# INA219_CH4.net
KiCad netlist of a schematic drawn in Altium Designer
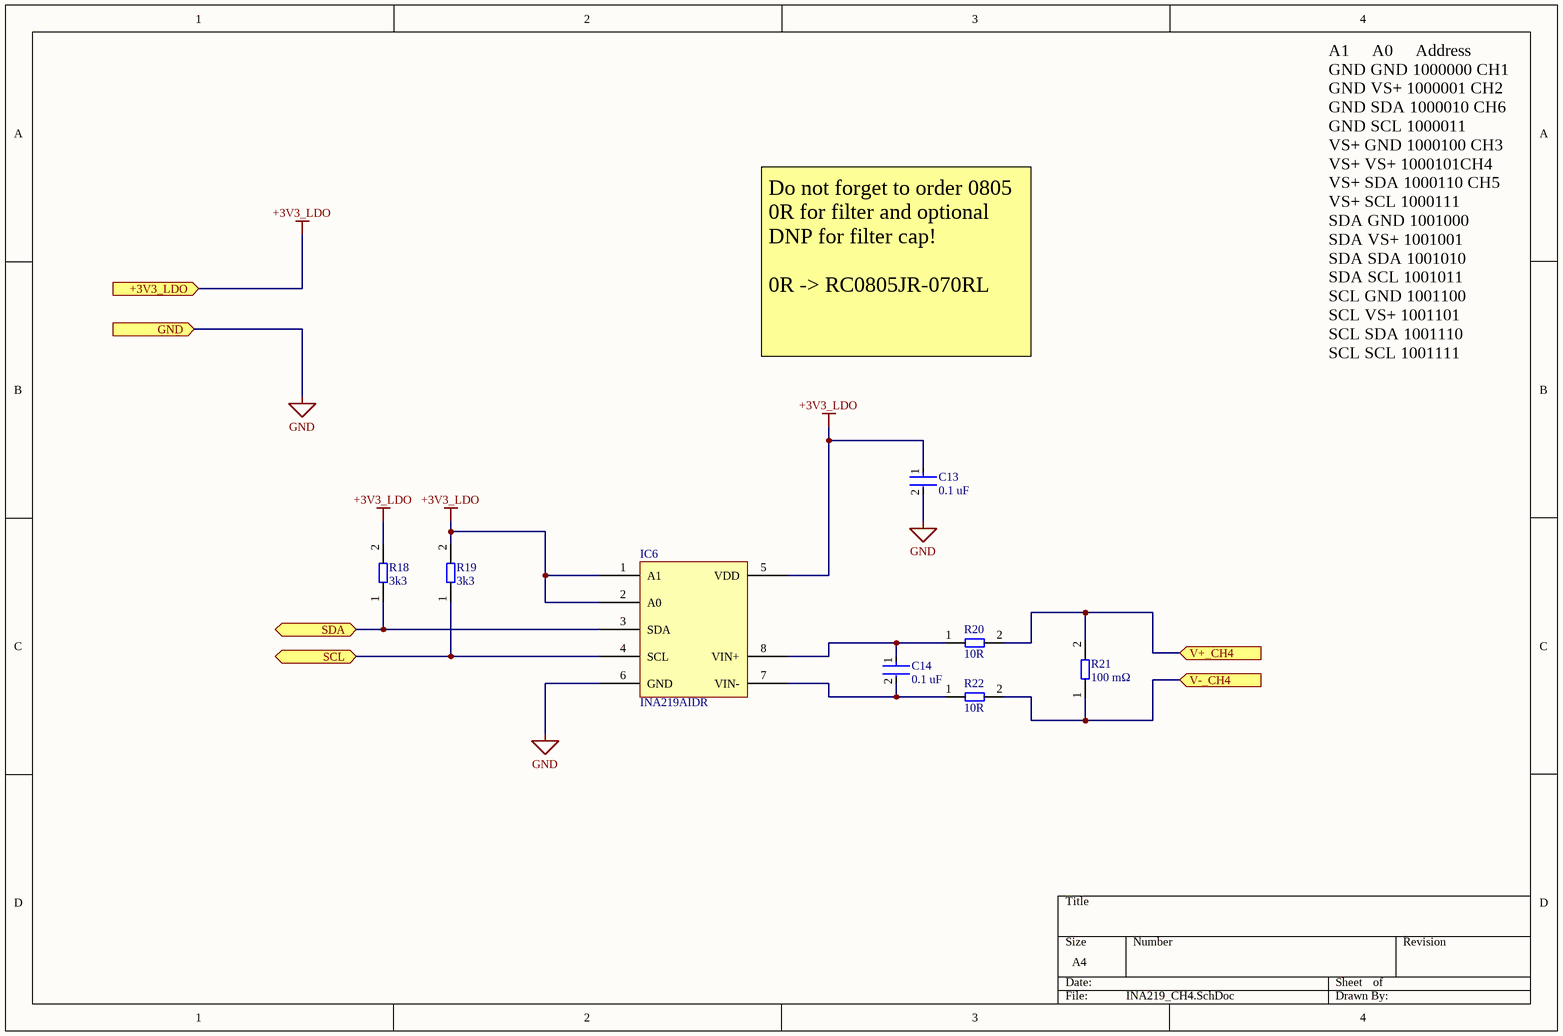
[diagram p0: INA219_CH4.SchDoc]

(export (version "E")
  (design (tool "Eeschema 10.0.6"))
  (components
    (comp (ref "C13")
      (value "0.1 uF")
      (footprint "FP-C0805C-DN-MFG")
      (description "C0805 0.10 μF X7R 30ppm/°C 20.00% 50 V C0805C104M5RAC")
      (fields
        (field (name "MANUFACTURER PART NUMBER") "C0805C104M5RAC")
        (field (name "MANUFACTURER") "KEMET")
      )
      (libsource (lib "Altium Content Vault") (part "b4654b650e69147ec39a6b967a45e02"))
    )
    (comp (ref "C14")
      (value "0.1 uF")
      (footprint "FP-C0805C-DN-MFG")
      (description "C0805 0.10 μF X7R 30ppm/°C 20.00% 50 V C0805C104M5RAC")
      (fields
        (field (name "MANUFACTURER PART NUMBER") "C0805C104M5RAC")
        (field (name "MANUFACTURER") "KEMET")
      )
      (libsource (lib "Altium Content Vault") (part "b4654b650e69147ec39a6b967a45e02"))
    )
    (comp (ref "IC6")
      (value "INA219AIDR")
      (footprint "INA219AIDR")
      (description "Current & Power Monitors & Regulators Zero-Drift,Bi-Dir Crnt/Pwr Monitor")
      (libsource (lib "Callisto Control Board") (part "INA219AIDR"))
    )
    (comp (ref "R18")
      (value "3k3")
      (footprint "0805 Resistor - IPC A")
      (description "Thick Film Resistors - SMD 3.3 kOhms 125 mW 0805 1%\r\nRE0805FRE073K3L")
      (libsource (lib "Callisto Control Board") (part "RE0805FRE073K3L"))
    )
    (comp (ref "R19")
      (value "3k3")
      (footprint "0805 Resistor - IPC A")
      (description "Thick Film Resistors - SMD 3.3 kOhms 125 mW 0805 1%\r\nRE0805FRE073K3L")
      (libsource (lib "Callisto Control Board") (part "RE0805FRE073K3L"))
    )
    (comp (ref "R20")
      (value "10R")
      (footprint "0805 Resistor - IPC A")
      (description "Thick Film Resistors - SMD 10 Ohms 125 mW 0805 1%\r\nRC0805FR-0710RL")
      (libsource (lib "Callisto Control Board") (part "RC0805FR-0710RL"))
    )
    (comp (ref "R21")
      (value "100 mΩ")
      (footprint "PE2512FKM070R1L")
      (description "Current Sense Resistors - SMD 100 mOhms 1 Watt 1 % 75 ppm/C AEC-Q200\r\nPE2512FKM070R1L")
      (libsource (lib "Callisto Control Board") (part "PE2512FKM070R1L"))
    )
    (comp (ref "R22")
      (value "10R")
      (footprint "0805 Resistor - IPC A")
      (description "Thick Film Resistors - SMD 10 Ohms 125 mW 0805 1%\r\nRC0805FR-0710RL")
      (libsource (lib "Callisto Control Board") (part "RC0805FR-0710RL"))
    )
  )
  (nets
    (net (code "1") (name "+3V3_LDO") (class "Default")
      (node (ref "C13") (pin "1") (pinfunction "1_1") (pintype "passive"))
      (node (ref "IC6") (pin "1") (pinfunction "A1_1") (pintype "passive"))
      (node (ref "IC6") (pin "2") (pinfunction "A0_2") (pintype "passive"))
      (node (ref "IC6") (pin "5") (pinfunction "VDD_5") (pintype "passive"))
      (node (ref "R18") (pin "2") (pintype "passive"))
      (node (ref "R19") (pin "2") (pintype "passive"))
    )
    (net (code "2") (name "/SCL") (class "Default")
      (node (ref "IC6") (pin "4") (pinfunction "SCL_4") (pintype "passive"))
      (node (ref "R19") (pin "1") (pintype "passive"))
    )
    (net (code "3") (name "/SDA") (class "Default")
      (node (ref "IC6") (pin "3") (pinfunction "SDA_3") (pintype "passive"))
      (node (ref "R18") (pin "1") (pintype "passive"))
    )
    (net (code "4") (name "/V+_CH4") (class "Default")
      (node (ref "R20") (pin "2") (pintype "passive"))
      (node (ref "R21") (pin "2") (pintype "passive"))
    )
    (net (code "5") (name "/V-_CH4") (class "Default")
      (node (ref "R21") (pin "1") (pintype "passive"))
      (node (ref "R22") (pin "2") (pintype "passive"))
    )
    (net (code "6") (name "GND") (class "Default")
      (node (ref "C13") (pin "2") (pinfunction "2_2") (pintype "passive"))
      (node (ref "IC6") (pin "6") (pinfunction "GND_6") (pintype "passive"))
    )
    (net (code "7") (name "Net-(IC6-VIN+)") (class "Default")
      (node (ref "C14") (pin "1") (pinfunction "1_1") (pintype "passive"))
      (node (ref "IC6") (pin "8") (pinfunction "VIN+_8") (pintype "passive"))
      (node (ref "R20") (pin "1") (pintype "passive"))
    )
    (net (code "8") (name "Net-(IC6-VIN-)") (class "Default")
      (node (ref "C14") (pin "2") (pinfunction "2_2") (pintype "passive"))
      (node (ref "IC6") (pin "7") (pinfunction "VIN-_7") (pintype "passive"))
      (node (ref "R22") (pin "1") (pintype "passive"))
    )
  )
)
